# fpga31-serdes-power.net
KiCad netlist of a schematic drawn in Altium Designer
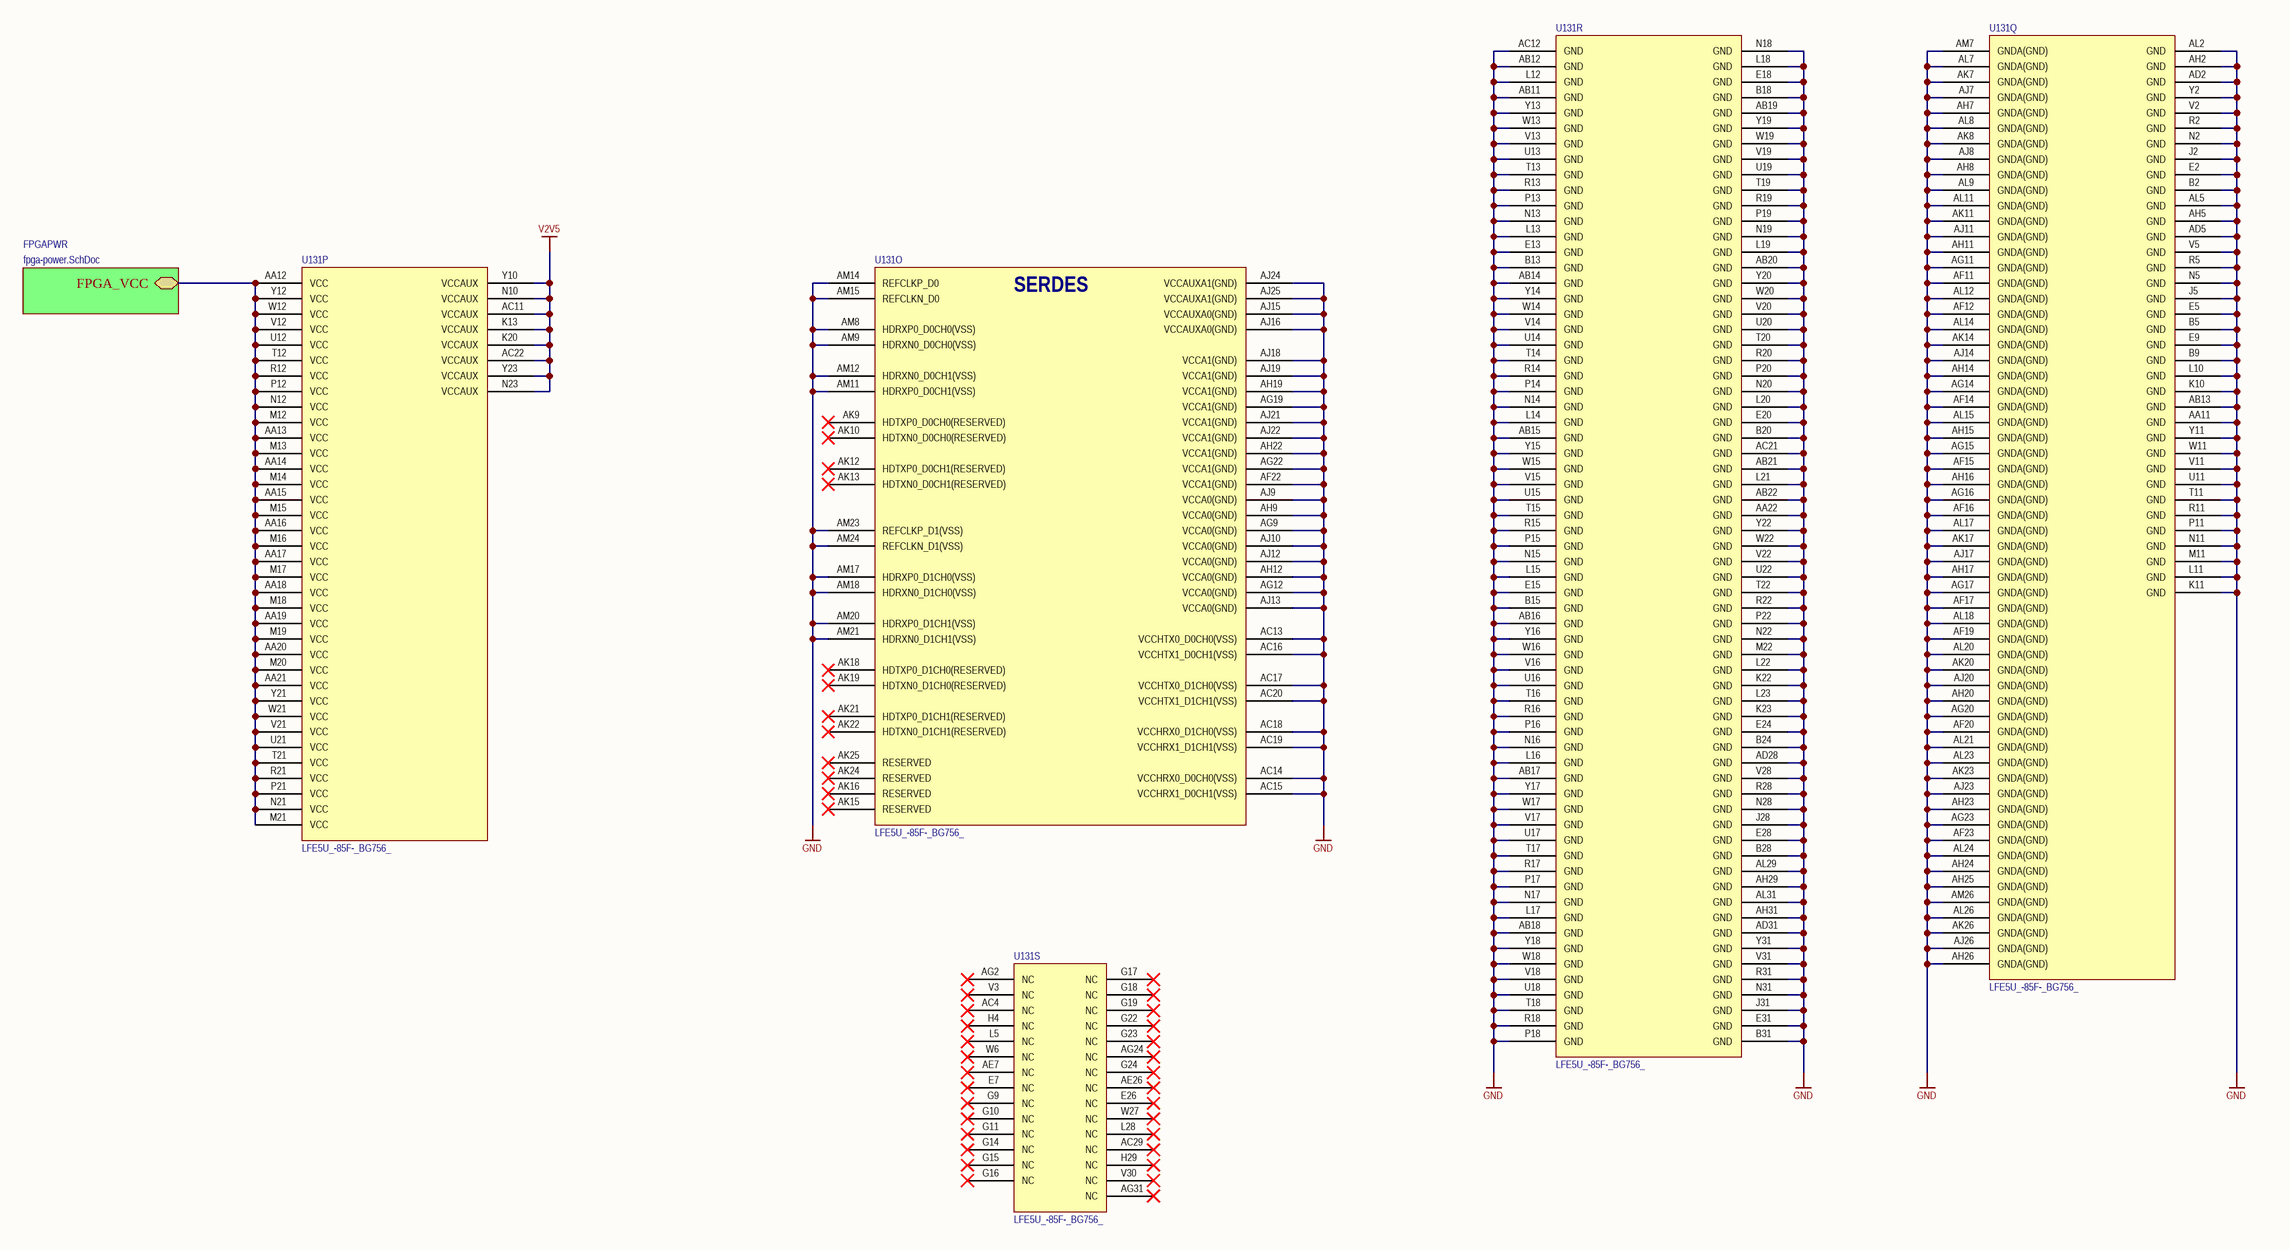
[diagram p0: fpga31-serdes-power.SchDoc]

(export (version "E")
  (design (tool "Eeschema 10.0.6"))
  (components
    (comp (ref "U131")
      (value "LFE5U_-85F-_BG756_")
      (footprint "lattice:caBGA756")
      (description "ECP5 FPGA, 85k LUT, 756-caBGA")
      (fields (field (name "MANUFACTURER") "Lattice Semiconductor"))
      (libsource (lib "lattice") (part "LFE5U_-85F-_BG756_"))
    )
  )
  (nets
    (net (code "1") (name "/FPGA_VCC") (class "Default")
      (node (ref "U131") (pin "AA12") (pinfunction "VCC_AA12") (pintype "power_in"))
      (node (ref "U131") (pin "AA13") (pinfunction "VCC_AA13") (pintype "power_in"))
      (node (ref "U131") (pin "AA14") (pinfunction "VCC_AA14") (pintype "power_in"))
      (node (ref "U131") (pin "AA15") (pinfunction "VCC_AA15") (pintype "power_in"))
      (node (ref "U131") (pin "AA16") (pinfunction "VCC_AA16") (pintype "power_in"))
      (node (ref "U131") (pin "AA17") (pinfunction "VCC_AA17") (pintype "power_in"))
      (node (ref "U131") (pin "AA18") (pinfunction "VCC_AA18") (pintype "power_in"))
      (node (ref "U131") (pin "AA19") (pinfunction "VCC_AA19") (pintype "power_in"))
      (node (ref "U131") (pin "AA20") (pinfunction "VCC_AA20") (pintype "power_in"))
      (node (ref "U131") (pin "AA21") (pinfunction "VCC_AA21") (pintype "power_in"))
      (node (ref "U131") (pin "M12") (pinfunction "VCC_M12") (pintype "power_in"))
      (node (ref "U131") (pin "M13") (pinfunction "VCC_M13") (pintype "power_in"))
      (node (ref "U131") (pin "M14") (pinfunction "VCC_M14") (pintype "power_in"))
      (node (ref "U131") (pin "M15") (pinfunction "VCC_M15") (pintype "power_in"))
      (node (ref "U131") (pin "M16") (pinfunction "VCC_M16") (pintype "power_in"))
      (node (ref "U131") (pin "M17") (pinfunction "VCC_M17") (pintype "power_in"))
      (node (ref "U131") (pin "M18") (pinfunction "VCC_M18") (pintype "power_in"))
      (node (ref "U131") (pin "M19") (pinfunction "VCC_M19") (pintype "power_in"))
      (node (ref "U131") (pin "M20") (pinfunction "VCC_M20") (pintype "power_in"))
      (node (ref "U131") (pin "M21") (pinfunction "VCC_M21") (pintype "power_in"))
      (node (ref "U131") (pin "N12") (pinfunction "VCC_N12") (pintype "power_in"))
      (node (ref "U131") (pin "N21") (pinfunction "VCC_N21") (pintype "power_in"))
      (node (ref "U131") (pin "P12") (pinfunction "VCC_P12") (pintype "power_in"))
      (node (ref "U131") (pin "P21") (pinfunction "VCC_P21") (pintype "power_in"))
      (node (ref "U131") (pin "R12") (pinfunction "VCC_R12") (pintype "power_in"))
      (node (ref "U131") (pin "R21") (pinfunction "VCC_R21") (pintype "power_in"))
      (node (ref "U131") (pin "T12") (pinfunction "VCC_T12") (pintype "power_in"))
      (node (ref "U131") (pin "T21") (pinfunction "VCC_T21") (pintype "power_in"))
      (node (ref "U131") (pin "U12") (pinfunction "VCC_U12") (pintype "power_in"))
      (node (ref "U131") (pin "U21") (pinfunction "VCC_U21") (pintype "power_in"))
      (node (ref "U131") (pin "V12") (pinfunction "VCC_V12") (pintype "power_in"))
      (node (ref "U131") (pin "V21") (pinfunction "VCC_V21") (pintype "power_in"))
      (node (ref "U131") (pin "W12") (pinfunction "VCC_W12") (pintype "power_in"))
      (node (ref "U131") (pin "W21") (pinfunction "VCC_W21") (pintype "power_in"))
      (node (ref "U131") (pin "Y12") (pinfunction "VCC_Y12") (pintype "power_in"))
      (node (ref "U131") (pin "Y21") (pinfunction "VCC_Y21") (pintype "power_in"))
    )
    (net (code "2") (name "GND") (class "Default")
      (node (ref "U131") (pin "AA11") (pinfunction "GND_AA11") (pintype "power_in"))
      (node (ref "U131") (pin "AA22") (pinfunction "GND_AA22") (pintype "power_in"))
      (node (ref "U131") (pin "AB11") (pinfunction "GND_AB11") (pintype "power_in"))
      (node (ref "U131") (pin "AB12") (pinfunction "GND_AB12") (pintype "power_in"))
      (node (ref "U131") (pin "AB13") (pinfunction "GND_AB13") (pintype "power_in"))
      (node (ref "U131") (pin "AB14") (pinfunction "GND_AB14") (pintype "power_in"))
      (node (ref "U131") (pin "AB15") (pinfunction "GND_AB15") (pintype "power_in"))
      (node (ref "U131") (pin "AB16") (pinfunction "GND_AB16") (pintype "power_in"))
      (node (ref "U131") (pin "AB17") (pinfunction "GND_AB17") (pintype "power_in"))
      (node (ref "U131") (pin "AB18") (pinfunction "GND_AB18") (pintype "power_in"))
      (node (ref "U131") (pin "AB19") (pinfunction "GND_AB19") (pintype "power_in"))
      (node (ref "U131") (pin "AB20") (pinfunction "GND_AB20") (pintype "power_in"))
      (node (ref "U131") (pin "AB21") (pinfunction "GND_AB21") (pintype "power_in"))
      (node (ref "U131") (pin "AB22") (pinfunction "GND_AB22") (pintype "power_in"))
      (node (ref "U131") (pin "AC12") (pinfunction "GND_AC12") (pintype "power_in"))
      (node (ref "U131") (pin "AC13") (pinfunction "VCCHTX0_D0CH0(VSS)_AC13") (pintype "power_in"))
      (node (ref "U131") (pin "AC14") (pinfunction "VCCHRX0_D0CH0(VSS)_AC14") (pintype "power_in"))
      (node (ref "U131") (pin "AC15") (pinfunction "VCCHRX1_D0CH1(VSS)_AC15") (pintype "power_in"))
      (node (ref "U131") (pin "AC16") (pinfunction "VCCHTX1_D0CH1(VSS)_AC16") (pintype "power_in"))
      (node (ref "U131") (pin "AC17") (pinfunction "VCCHTX0_D1CH0(VSS)_AC17") (pintype "power_in"))
      (node (ref "U131") (pin "AC18") (pinfunction "VCCHRX0_D1CH0(VSS)_AC18") (pintype "power_in"))
      (node (ref "U131") (pin "AC19") (pinfunction "VCCHRX1_D1CH1(VSS)_AC19") (pintype "power_in"))
      (node (ref "U131") (pin "AC20") (pinfunction "VCCHTX1_D1CH1(VSS)_AC20") (pintype "power_in"))
      (node (ref "U131") (pin "AC21") (pinfunction "GND_AC21") (pintype "power_in"))
      (node (ref "U131") (pin "AD2") (pinfunction "GND_AD2") (pintype "power_in"))
      (node (ref "U131") (pin "AD28") (pinfunction "GND_AD28") (pintype "power_in"))
      (node (ref "U131") (pin "AD31") (pinfunction "GND_AD31") (pintype "power_in"))
      (node (ref "U131") (pin "AD5") (pinfunction "GND_AD5") (pintype "power_in"))
      (node (ref "U131") (pin "AF11") (pinfunction "GNDA(GND)_AF11") (pintype "power_in"))
      (node (ref "U131") (pin "AF12") (pinfunction "GNDA(GND)_AF12") (pintype "power_in"))
      (node (ref "U131") (pin "AF14") (pinfunction "GNDA(GND)_AF14") (pintype "power_in"))
      (node (ref "U131") (pin "AF15") (pinfunction "GNDA(GND)_AF15") (pintype "power_in"))
      (node (ref "U131") (pin "AF16") (pinfunction "GNDA(GND)_AF16") (pintype "power_in"))
      (node (ref "U131") (pin "AF17") (pinfunction "GNDA(GND)_AF17") (pintype "power_in"))
      (node (ref "U131") (pin "AF19") (pinfunction "GNDA(GND)_AF19") (pintype "power_in"))
      (node (ref "U131") (pin "AF20") (pinfunction "GNDA(GND)_AF20") (pintype "power_in"))
      (node (ref "U131") (pin "AF22") (pinfunction "VCCA1(GND)_AF22") (pintype "power_in"))
      (node (ref "U131") (pin "AF23") (pinfunction "GNDA(GND)_AF23") (pintype "power_in"))
      (node (ref "U131") (pin "AG11") (pinfunction "GNDA(GND)_AG11") (pintype "power_in"))
      (node (ref "U131") (pin "AG12") (pinfunction "VCCA0(GND)_AG12") (pintype "power_in"))
      (node (ref "U131") (pin "AG14") (pinfunction "GNDA(GND)_AG14") (pintype "power_in"))
      (node (ref "U131") (pin "AG15") (pinfunction "GNDA(GND)_AG15") (pintype "power_in"))
      (node (ref "U131") (pin "AG16") (pinfunction "GNDA(GND)_AG16") (pintype "power_in"))
      (node (ref "U131") (pin "AG17") (pinfunction "GNDA(GND)_AG17") (pintype "power_in"))
      (node (ref "U131") (pin "AG19") (pinfunction "VCCA1(GND)_AG19") (pintype "power_in"))
      (node (ref "U131") (pin "AG20") (pinfunction "GNDA(GND)_AG20") (pintype "power_in"))
      (node (ref "U131") (pin "AG22") (pinfunction "VCCA1(GND)_AG22") (pintype "power_in"))
      (node (ref "U131") (pin "AG23") (pinfunction "GNDA(GND)_AG23") (pintype "power_in"))
      (node (ref "U131") (pin "AG9") (pinfunction "VCCA0(GND)_AG9") (pintype "power_in"))
      (node (ref "U131") (pin "AH11") (pinfunction "GNDA(GND)_AH11") (pintype "power_in"))
      (node (ref "U131") (pin "AH12") (pinfunction "VCCA0(GND)_AH12") (pintype "power_in"))
      (node (ref "U131") (pin "AH14") (pinfunction "GNDA(GND)_AH14") (pintype "power_in"))
      (node (ref "U131") (pin "AH15") (pinfunction "GNDA(GND)_AH15") (pintype "power_in"))
      (node (ref "U131") (pin "AH16") (pinfunction "GNDA(GND)_AH16") (pintype "power_in"))
      (node (ref "U131") (pin "AH17") (pinfunction "GNDA(GND)_AH17") (pintype "power_in"))
      (node (ref "U131") (pin "AH19") (pinfunction "VCCA1(GND)_AH19") (pintype "power_in"))
      (node (ref "U131") (pin "AH2") (pinfunction "GND_AH2") (pintype "power_in"))
      (node (ref "U131") (pin "AH20") (pinfunction "GNDA(GND)_AH20") (pintype "power_in"))
      (node (ref "U131") (pin "AH22") (pinfunction "VCCA1(GND)_AH22") (pintype "power_in"))
      (node (ref "U131") (pin "AH23") (pinfunction "GNDA(GND)_AH23") (pintype "power_in"))
      (node (ref "U131") (pin "AH24") (pinfunction "GNDA(GND)_AH24") (pintype "power_in"))
      (node (ref "U131") (pin "AH25") (pinfunction "GNDA(GND)_AH25") (pintype "power_in"))
      (node (ref "U131") (pin "AH26") (pinfunction "GNDA(GND)_AH26") (pintype "power_in"))
      (node (ref "U131") (pin "AH29") (pinfunction "GND_AH29") (pintype "power_in"))
      (node (ref "U131") (pin "AH31") (pinfunction "GND_AH31") (pintype "power_in"))
      (node (ref "U131") (pin "AH5") (pinfunction "GND_AH5") (pintype "power_in"))
      (node (ref "U131") (pin "AH7") (pinfunction "GNDA(GND)_AH7") (pintype "power_in"))
      (node (ref "U131") (pin "AH8") (pinfunction "GNDA(GND)_AH8") (pintype "power_in"))
      (node (ref "U131") (pin "AH9") (pinfunction "VCCA0(GND)_AH9") (pintype "power_in"))
      (node (ref "U131") (pin "AJ10") (pinfunction "VCCA0(GND)_AJ10") (pintype "power_in"))
      (node (ref "U131") (pin "AJ11") (pinfunction "GNDA(GND)_AJ11") (pintype "power_in"))
      (node (ref "U131") (pin "AJ12") (pinfunction "VCCA0(GND)_AJ12") (pintype "power_in"))
      (node (ref "U131") (pin "AJ13") (pinfunction "VCCA0(GND)_AJ13") (pintype "power_in"))
      (node (ref "U131") (pin "AJ14") (pinfunction "GNDA(GND)_AJ14") (pintype "power_in"))
      (node (ref "U131") (pin "AJ15") (pinfunction "VCCAUXA0(GND)_AJ15") (pintype "power_in"))
      (node (ref "U131") (pin "AJ16") (pinfunction "VCCAUXA0(GND)_AJ16") (pintype "power_in"))
      (node (ref "U131") (pin "AJ17") (pinfunction "GNDA(GND)_AJ17") (pintype "power_in"))
      (node (ref "U131") (pin "AJ18") (pinfunction "VCCA1(GND)_AJ18") (pintype "power_in"))
      (node (ref "U131") (pin "AJ19") (pinfunction "VCCA1(GND)_AJ19") (pintype "power_in"))
      (node (ref "U131") (pin "AJ20") (pinfunction "GNDA(GND)_AJ20") (pintype "power_in"))
      (node (ref "U131") (pin "AJ21") (pinfunction "VCCA1(GND)_AJ21") (pintype "power_in"))
      (node (ref "U131") (pin "AJ22") (pinfunction "VCCA1(GND)_AJ22") (pintype "power_in"))
      (node (ref "U131") (pin "AJ23") (pinfunction "GNDA(GND)_AJ23") (pintype "power_in"))
      (node (ref "U131") (pin "AJ24") (pinfunction "VCCAUXA1(GND)_AJ24") (pintype "power_in"))
      (node (ref "U131") (pin "AJ25") (pinfunction "VCCAUXA1(GND)_AJ25") (pintype "power_in"))
      (node (ref "U131") (pin "AJ26") (pinfunction "GNDA(GND)_AJ26") (pintype "power_in"))
      (node (ref "U131") (pin "AJ7") (pinfunction "GNDA(GND)_AJ7") (pintype "power_in"))
      (node (ref "U131") (pin "AJ8") (pinfunction "GNDA(GND)_AJ8") (pintype "power_in"))
      (node (ref "U131") (pin "AJ9") (pinfunction "VCCA0(GND)_AJ9") (pintype "power_in"))
      (node (ref "U131") (pin "AK11") (pinfunction "GNDA(GND)_AK11") (pintype "power_in"))
      (node (ref "U131") (pin "AK14") (pinfunction "GNDA(GND)_AK14") (pintype "power_in"))
      (node (ref "U131") (pin "AK17") (pinfunction "GNDA(GND)_AK17") (pintype "power_in"))
      (node (ref "U131") (pin "AK20") (pinfunction "GNDA(GND)_AK20") (pintype "power_in"))
      (node (ref "U131") (pin "AK23") (pinfunction "GNDA(GND)_AK23") (pintype "power_in"))
      (node (ref "U131") (pin "AK26") (pinfunction "GNDA(GND)_AK26") (pintype "power_in"))
      (node (ref "U131") (pin "AK7") (pinfunction "GNDA(GND)_AK7") (pintype "power_in"))
      (node (ref "U131") (pin "AK8") (pinfunction "GNDA(GND)_AK8") (pintype "power_in"))
      (node (ref "U131") (pin "AL11") (pinfunction "GNDA(GND)_AL11") (pintype "power_in"))
      (node (ref "U131") (pin "AL12") (pinfunction "GNDA(GND)_AL12") (pintype "power_in"))
      (node (ref "U131") (pin "AL14") (pinfunction "GNDA(GND)_AL14") (pintype "power_in"))
      (node (ref "U131") (pin "AL15") (pinfunction "GNDA(GND)_AL15") (pintype "power_in"))
      (node (ref "U131") (pin "AL17") (pinfunction "GNDA(GND)_AL17") (pintype "power_in"))
      (node (ref "U131") (pin "AL18") (pinfunction "GNDA(GND)_AL18") (pintype "power_in"))
      (node (ref "U131") (pin "AL2") (pinfunction "GND_AL2") (pintype "power_in"))
      (node (ref "U131") (pin "AL20") (pinfunction "GNDA(GND)_AL20") (pintype "power_in"))
      (node (ref "U131") (pin "AL21") (pinfunction "GNDA(GND)_AL21") (pintype "power_in"))
      (node (ref "U131") (pin "AL23") (pinfunction "GNDA(GND)_AL23") (pintype "power_in"))
      (node (ref "U131") (pin "AL24") (pinfunction "GNDA(GND)_AL24") (pintype "power_in"))
      (node (ref "U131") (pin "AL26") (pinfunction "GNDA(GND)_AL26") (pintype "power_in"))
      (node (ref "U131") (pin "AL29") (pinfunction "GND_AL29") (pintype "power_in"))
      (node (ref "U131") (pin "AL31") (pinfunction "GND_AL31") (pintype "power_in"))
      (node (ref "U131") (pin "AL5") (pinfunction "GND_AL5") (pintype "power_in"))
      (node (ref "U131") (pin "AL7") (pinfunction "GNDA(GND)_AL7") (pintype "power_in"))
      (node (ref "U131") (pin "AL8") (pinfunction "GNDA(GND)_AL8") (pintype "power_in"))
      (node (ref "U131") (pin "AL9") (pinfunction "GNDA(GND)_AL9") (pintype "power_in"))
      (node (ref "U131") (pin "AM11") (pinfunction "HDRXP0_D0CH1(VSS)_AM11") (pintype "passive"))
      (node (ref "U131") (pin "AM12") (pinfunction "HDRXN0_D0CH1(VSS)_AM12") (pintype "passive"))
      (node (ref "U131") (pin "AM14") (pinfunction "REFCLKP_D0_AM14") (pintype "passive"))
      (node (ref "U131") (pin "AM15") (pinfunction "REFCLKN_D0_AM15") (pintype "passive"))
      (node (ref "U131") (pin "AM17") (pinfunction "HDRXP0_D1CH0(VSS)_AM17") (pintype "passive"))
      (node (ref "U131") (pin "AM18") (pinfunction "HDRXN0_D1CH0(VSS)_AM18") (pintype "passive"))
      (node (ref "U131") (pin "AM20") (pinfunction "HDRXP0_D1CH1(VSS)_AM20") (pintype "passive"))
      (node (ref "U131") (pin "AM21") (pinfunction "HDRXN0_D1CH1(VSS)_AM21") (pintype "passive"))
      (node (ref "U131") (pin "AM23") (pinfunction "REFCLKP_D1(VSS)_AM23") (pintype "passive"))
      (node (ref "U131") (pin "AM24") (pinfunction "REFCLKN_D1(VSS)_AM24") (pintype "passive"))
      (node (ref "U131") (pin "AM26") (pinfunction "GNDA(GND)_AM26") (pintype "power_in"))
      (node (ref "U131") (pin "AM7") (pinfunction "GNDA(GND)_AM7") (pintype "power_in"))
      (node (ref "U131") (pin "AM8") (pinfunction "HDRXP0_D0CH0(VSS)_AM8") (pintype "passive"))
      (node (ref "U131") (pin "AM9") (pinfunction "HDRXN0_D0CH0(VSS)_AM9") (pintype "passive"))
      (node (ref "U131") (pin "B13") (pinfunction "GND_B13") (pintype "power_in"))
      (node (ref "U131") (pin "B15") (pinfunction "GND_B15") (pintype "power_in"))
      (node (ref "U131") (pin "B18") (pinfunction "GND_B18") (pintype "power_in"))
      (node (ref "U131") (pin "B2") (pinfunction "GND_B2") (pintype "power_in"))
      (node (ref "U131") (pin "B20") (pinfunction "GND_B20") (pintype "power_in"))
      (node (ref "U131") (pin "B24") (pinfunction "GND_B24") (pintype "power_in"))
      (node (ref "U131") (pin "B28") (pinfunction "GND_B28") (pintype "power_in"))
      (node (ref "U131") (pin "B31") (pinfunction "GND_B31") (pintype "power_in"))
      (node (ref "U131") (pin "B5") (pinfunction "GND_B5") (pintype "power_in"))
      (node (ref "U131") (pin "B9") (pinfunction "GND_B9") (pintype "power_in"))
      (node (ref "U131") (pin "E13") (pinfunction "GND_E13") (pintype "power_in"))
      (node (ref "U131") (pin "E15") (pinfunction "GND_E15") (pintype "power_in"))
      (node (ref "U131") (pin "E18") (pinfunction "GND_E18") (pintype "power_in"))
      (node (ref "U131") (pin "E2") (pinfunction "GND_E2") (pintype "power_in"))
      (node (ref "U131") (pin "E20") (pinfunction "GND_E20") (pintype "power_in"))
      (node (ref "U131") (pin "E24") (pinfunction "GND_E24") (pintype "power_in"))
      (node (ref "U131") (pin "E28") (pinfunction "GND_E28") (pintype "power_in"))
      (node (ref "U131") (pin "E31") (pinfunction "GND_E31") (pintype "power_in"))
      (node (ref "U131") (pin "E5") (pinfunction "GND_E5") (pintype "power_in"))
      (node (ref "U131") (pin "E9") (pinfunction "GND_E9") (pintype "power_in"))
      (node (ref "U131") (pin "J2") (pinfunction "GND_J2") (pintype "power_in"))
      (node (ref "U131") (pin "J28") (pinfunction "GND_J28") (pintype "power_in"))
      (node (ref "U131") (pin "J31") (pinfunction "GND_J31") (pintype "power_in"))
      (node (ref "U131") (pin "J5") (pinfunction "GND_J5") (pintype "power_in"))
      (node (ref "U131") (pin "K10") (pinfunction "GND_K10") (pintype "power_in"))
      (node (ref "U131") (pin "K11") (pinfunction "GND_K11") (pintype "power_in"))
      (node (ref "U131") (pin "K22") (pinfunction "GND_K22") (pintype "power_in"))
      (node (ref "U131") (pin "K23") (pinfunction "GND_K23") (pintype "power_in"))
      (node (ref "U131") (pin "L10") (pinfunction "GND_L10") (pintype "power_in"))
      (node (ref "U131") (pin "L11") (pinfunction "GND_L11") (pintype "power_in"))
      (node (ref "U131") (pin "L12") (pinfunction "GND_L12") (pintype "power_in"))
      (node (ref "U131") (pin "L13") (pinfunction "GND_L13") (pintype "power_in"))
      (node (ref "U131") (pin "L14") (pinfunction "GND_L14") (pintype "power_in"))
      (node (ref "U131") (pin "L15") (pinfunction "GND_L15") (pintype "power_in"))
      (node (ref "U131") (pin "L16") (pinfunction "GND_L16") (pintype "power_in"))
      (node (ref "U131") (pin "L17") (pinfunction "GND_L17") (pintype "power_in"))
      (node (ref "U131") (pin "L18") (pinfunction "GND_L18") (pintype "power_in"))
      (node (ref "U131") (pin "L19") (pinfunction "GND_L19") (pintype "power_in"))
      (node (ref "U131") (pin "L20") (pinfunction "GND_L20") (pintype "power_in"))
      (node (ref "U131") (pin "L21") (pinfunction "GND_L21") (pintype "power_in"))
      (node (ref "U131") (pin "L22") (pinfunction "GND_L22") (pintype "power_in"))
      (node (ref "U131") (pin "L23") (pinfunction "GND_L23") (pintype "power_in"))
      (node (ref "U131") (pin "M11") (pinfunction "GND_M11") (pintype "power_in"))
      (node (ref "U131") (pin "M22") (pinfunction "GND_M22") (pintype "power_in"))
      (node (ref "U131") (pin "N11") (pinfunction "GND_N11") (pintype "power_in"))
      (node (ref "U131") (pin "N13") (pinfunction "GND_N13") (pintype "power_in"))
      (node (ref "U131") (pin "N14") (pinfunction "GND_N14") (pintype "power_in"))
      (node (ref "U131") (pin "N15") (pinfunction "GND_N15") (pintype "power_in"))
      (node (ref "U131") (pin "N16") (pinfunction "GND_N16") (pintype "power_in"))
      (node (ref "U131") (pin "N17") (pinfunction "GND_N17") (pintype "power_in"))
      (node (ref "U131") (pin "N18") (pinfunction "GND_N18") (pintype "power_in"))
      (node (ref "U131") (pin "N19") (pinfunction "GND_N19") (pintype "power_in"))
      (node (ref "U131") (pin "N2") (pinfunction "GND_N2") (pintype "power_in"))
      (node (ref "U131") (pin "N20") (pinfunction "GND_N20") (pintype "power_in"))
      (node (ref "U131") (pin "N22") (pinfunction "GND_N22") (pintype "power_in"))
      (node (ref "U131") (pin "N28") (pinfunction "GND_N28") (pintype "power_in"))
      (node (ref "U131") (pin "N31") (pinfunction "GND_N31") (pintype "power_in"))
      (node (ref "U131") (pin "N5") (pinfunction "GND_N5") (pintype "power_in"))
      (node (ref "U131") (pin "P11") (pinfunction "GND_P11") (pintype "power_in"))
      (node (ref "U131") (pin "P13") (pinfunction "GND_P13") (pintype "power_in"))
      (node (ref "U131") (pin "P14") (pinfunction "GND_P14") (pintype "power_in"))
      (node (ref "U131") (pin "P15") (pinfunction "GND_P15") (pintype "power_in"))
      (node (ref "U131") (pin "P16") (pinfunction "GND_P16") (pintype "power_in"))
      (node (ref "U131") (pin "P17") (pinfunction "GND_P17") (pintype "power_in"))
      (node (ref "U131") (pin "P18") (pinfunction "GND_P18") (pintype "power_in"))
      (node (ref "U131") (pin "P19") (pinfunction "GND_P19") (pintype "power_in"))
      (node (ref "U131") (pin "P20") (pinfunction "GND_P20") (pintype "power_in"))
      (node (ref "U131") (pin "P22") (pinfunction "GND_P22") (pintype "power_in"))
      (node (ref "U131") (pin "R11") (pinfunction "GND_R11") (pintype "power_in"))
      (node (ref "U131") (pin "R13") (pinfunction "GND_R13") (pintype "power_in"))
      (node (ref "U131") (pin "R14") (pinfunction "GND_R14") (pintype "power_in"))
      (node (ref "U131") (pin "R15") (pinfunction "GND_R15") (pintype "power_in"))
      (node (ref "U131") (pin "R16") (pinfunction "GND_R16") (pintype "power_in"))
      (node (ref "U131") (pin "R17") (pinfunction "GND_R17") (pintype "power_in"))
      (node (ref "U131") (pin "R18") (pinfunction "GND_R18") (pintype "power_in"))
      (node (ref "U131") (pin "R19") (pinfunction "GND_R19") (pintype "power_in"))
      (node (ref "U131") (pin "R2") (pinfunction "GND_R2") (pintype "power_in"))
      (node (ref "U131") (pin "R20") (pinfunction "GND_R20") (pintype "power_in"))
      (node (ref "U131") (pin "R22") (pinfunction "GND_R22") (pintype "power_in"))
      (node (ref "U131") (pin "R28") (pinfunction "GND_R28") (pintype "power_in"))
      (node (ref "U131") (pin "R31") (pinfunction "GND_R31") (pintype "power_in"))
      (node (ref "U131") (pin "R5") (pinfunction "GND_R5") (pintype "power_in"))
      (node (ref "U131") (pin "T11") (pinfunction "GND_T11") (pintype "power_in"))
      (node (ref "U131") (pin "T13") (pinfunction "GND_T13") (pintype "power_in"))
      (node (ref "U131") (pin "T14") (pinfunction "GND_T14") (pintype "power_in"))
      (node (ref "U131") (pin "T15") (pinfunction "GND_T15") (pintype "power_in"))
      (node (ref "U131") (pin "T16") (pinfunction "GND_T16") (pintype "power_in"))
      (node (ref "U131") (pin "T17") (pinfunction "GND_T17") (pintype "power_in"))
      (node (ref "U131") (pin "T18") (pinfunction "GND_T18") (pintype "power_in"))
      (node (ref "U131") (pin "T19") (pinfunction "GND_T19") (pintype "power_in"))
      (node (ref "U131") (pin "T20") (pinfunction "GND_T20") (pintype "power_in"))
      (node (ref "U131") (pin "T22") (pinfunction "GND_T22") (pintype "power_in"))
      (node (ref "U131") (pin "U11") (pinfunction "GND_U11") (pintype "power_in"))
      (node (ref "U131") (pin "U13") (pinfunction "GND_U13") (pintype "power_in"))
      (node (ref "U131") (pin "U14") (pinfunction "GND_U14") (pintype "power_in"))
      (node (ref "U131") (pin "U15") (pinfunction "GND_U15") (pintype "power_in"))
      (node (ref "U131") (pin "U16") (pinfunction "GND_U16") (pintype "power_in"))
      (node (ref "U131") (pin "U17") (pinfunction "GND_U17") (pintype "power_in"))
      (node (ref "U131") (pin "U18") (pinfunction "GND_U18") (pintype "power_in"))
      (node (ref "U131") (pin "U19") (pinfunction "GND_U19") (pintype "power_in"))
      (node (ref "U131") (pin "U20") (pinfunction "GND_U20") (pintype "power_in"))
      (node (ref "U131") (pin "U22") (pinfunction "GND_U22") (pintype "power_in"))
      (node (ref "U131") (pin "V11") (pinfunction "GND_V11") (pintype "power_in"))
      (node (ref "U131") (pin "V13") (pinfunction "GND_V13") (pintype "power_in"))
      (node (ref "U131") (pin "V14") (pinfunction "GND_V14") (pintype "power_in"))
      (node (ref "U131") (pin "V15") (pinfunction "GND_V15") (pintype "power_in"))
      (node (ref "U131") (pin "V16") (pinfunction "GND_V16") (pintype "power_in"))
      (node (ref "U131") (pin "V17") (pinfunction "GND_V17") (pintype "power_in"))
      (node (ref "U131") (pin "V18") (pinfunction "GND_V18") (pintype "power_in"))
      (node (ref "U131") (pin "V19") (pinfunction "GND_V19") (pintype "power_in"))
      (node (ref "U131") (pin "V2") (pinfunction "GND_V2") (pintype "power_in"))
      (node (ref "U131") (pin "V20") (pinfunction "GND_V20") (pintype "power_in"))
      (node (ref "U131") (pin "V22") (pinfunction "GND_V22") (pintype "power_in"))
      (node (ref "U131") (pin "V28") (pinfunction "GND_V28") (pintype "power_in"))
      (node (ref "U131") (pin "V31") (pinfunction "GND_V31") (pintype "power_in"))
      (node (ref "U131") (pin "V5") (pinfunction "GND_V5") (pintype "power_in"))
      (node (ref "U131") (pin "W11") (pinfunction "GND_W11") (pintype "power_in"))
      (node (ref "U131") (pin "W13") (pinfunction "GND_W13") (pintype "power_in"))
      (node (ref "U131") (pin "W14") (pinfunction "GND_W14") (pintype "power_in"))
      (node (ref "U131") (pin "W15") (pinfunction "GND_W15") (pintype "power_in"))
      (node (ref "U131") (pin "W16") (pinfunction "GND_W16") (pintype "power_in"))
      (node (ref "U131") (pin "W17") (pinfunction "GND_W17") (pintype "power_in"))
      (node (ref "U131") (pin "W18") (pinfunction "GND_W18") (pintype "power_in"))
      (node (ref "U131") (pin "W19") (pinfunction "GND_W19") (pintype "power_in"))
      (node (ref "U131") (pin "W20") (pinfunction "GND_W20") (pintype "power_in"))
      (node (ref "U131") (pin "W22") (pinfunction "GND_W22") (pintype "power_in"))
      (node (ref "U131") (pin "Y11") (pinfunction "GND_Y11") (pintype "power_in"))
      (node (ref "U131") (pin "Y13") (pinfunction "GND_Y13") (pintype "power_in"))
      (node (ref "U131") (pin "Y14") (pinfunction "GND_Y14") (pintype "power_in"))
      (node (ref "U131") (pin "Y15") (pinfunction "GND_Y15") (pintype "power_in"))
      (node (ref "U131") (pin "Y16") (pinfunction "GND_Y16") (pintype "power_in"))
      (node (ref "U131") (pin "Y17") (pinfunction "GND_Y17") (pintype "power_in"))
      (node (ref "U131") (pin "Y18") (pinfunction "GND_Y18") (pintype "power_in"))
      (node (ref "U131") (pin "Y19") (pinfunction "GND_Y19") (pintype "power_in"))
      (node (ref "U131") (pin "Y2") (pinfunction "GND_Y2") (pintype "power_in"))
      (node (ref "U131") (pin "Y20") (pinfunction "GND_Y20") (pintype "power_in"))
      (node (ref "U131") (pin "Y22") (pinfunction "GND_Y22") (pintype "power_in"))
      (node (ref "U131") (pin "Y31") (pinfunction "GND_Y31") (pintype "power_in"))
    )
    (net (code "3") (name "V2V5") (class "Default")
      (node (ref "U131") (pin "AC11") (pinfunction "VCCAUX_AC11") (pintype "power_in"))
      (node (ref "U131") (pin "AC22") (pinfunction "VCCAUX_AC22") (pintype "power_in"))
      (node (ref "U131") (pin "K13") (pinfunction "VCCAUX_K13") (pintype "power_in"))
      (node (ref "U131") (pin "K20") (pinfunction "VCCAUX_K20") (pintype "power_in"))
      (node (ref "U131") (pin "N10") (pinfunction "VCCAUX_N10") (pintype "power_in"))
      (node (ref "U131") (pin "N23") (pinfunction "VCCAUX_N23") (pintype "power_in"))
      (node (ref "U131") (pin "Y10") (pinfunction "VCCAUX_Y10") (pintype "power_in"))
      (node (ref "U131") (pin "Y23") (pinfunction "VCCAUX_Y23") (pintype "power_in"))
    )
    (net (code "4") (name "unconnected-(U131O-HDTXN0_D0CH0(RESERVED)-PadAK10)") (class "Default")
      (node (ref "U131") (pin "AK10") (pinfunction "HDTXN0_D0CH0(RESERVED)_AK10") (pintype "passive+no_connect"))
    )
    (net (code "5") (name "unconnected-(U131O-HDTXN0_D0CH1(RESERVED)-PadAK13)") (class "Default")
      (node (ref "U131") (pin "AK13") (pinfunction "HDTXN0_D0CH1(RESERVED)_AK13") (pintype "passive+no_connect"))
    )
    (net (code "6") (name "unconnected-(U131O-HDTXN0_D1CH0(RESERVED)-PadAK19)") (class "Default")
      (node (ref "U131") (pin "AK19") (pinfunction "HDTXN0_D1CH0(RESERVED)_AK19") (pintype "passive+no_connect"))
    )
    (net (code "7") (name "unconnected-(U131O-HDTXN0_D1CH1(RESERVED)-PadAK22)") (class "Default")
      (node (ref "U131") (pin "AK22") (pinfunction "HDTXN0_D1CH1(RESERVED)_AK22") (pintype "passive+no_connect"))
    )
    (net (code "8") (name "unconnected-(U131O-HDTXP0_D0CH0(RESERVED)-PadAK9)") (class "Default")
      (node (ref "U131") (pin "AK9") (pinfunction "HDTXP0_D0CH0(RESERVED)_AK9") (pintype "passive+no_connect"))
    )
    (net (code "9") (name "unconnected-(U131O-HDTXP0_D0CH1(RESERVED)-PadAK12)") (class "Default")
      (node (ref "U131") (pin "AK12") (pinfunction "HDTXP0_D0CH1(RESERVED)_AK12") (pintype "passive+no_connect"))
    )
    (net (code "10") (name "unconnected-(U131O-HDTXP0_D1CH0(RESERVED)-PadAK18)") (class "Default")
      (node (ref "U131") (pin "AK18") (pinfunction "HDTXP0_D1CH0(RESERVED)_AK18") (pintype "passive+no_connect"))
    )
    (net (code "11") (name "unconnected-(U131O-HDTXP0_D1CH1(RESERVED)-PadAK21)") (class "Default")
      (node (ref "U131") (pin "AK21") (pinfunction "HDTXP0_D1CH1(RESERVED)_AK21") (pintype "passive+no_connect"))
    )
    (net (code "12") (name "unconnected-(U131O-RESERVED-PadAK15)") (class "Default")
      (node (ref "U131") (pin "AK15") (pinfunction "RESERVED_AK15") (pintype "passive+no_connect"))
    )
    (net (code "13") (name "unconnected-(U131O-RESERVED-PadAK16)") (class "Default")
      (node (ref "U131") (pin "AK16") (pinfunction "RESERVED_AK16") (pintype "passive+no_connect"))
    )
    (net (code "14") (name "unconnected-(U131O-RESERVED-PadAK24)") (class "Default")
      (node (ref "U131") (pin "AK24") (pinfunction "RESERVED_AK24") (pintype "passive+no_connect"))
    )
    (net (code "15") (name "unconnected-(U131O-RESERVED-PadAK25)") (class "Default")
      (node (ref "U131") (pin "AK25") (pinfunction "RESERVED_AK25") (pintype "passive+no_connect"))
    )
    (net (code "16") (name "unconnected-(U131S-NC-PadAC4)") (class "Default")
      (node (ref "U131") (pin "AC4") (pinfunction "NC_AC4") (pintype "passive+no_connect"))
    )
    (net (code "17") (name "unconnected-(U131S-NC-PadAC29)") (class "Default")
      (node (ref "U131") (pin "AC29") (pinfunction "NC_AC29") (pintype "passive+no_connect"))
    )
    (net (code "18") (name "unconnected-(U131S-NC-PadAE7)") (class "Default")
      (node (ref "U131") (pin "AE7") (pinfunction "NC_AE7") (pintype "passive+no_connect"))
    )
    (net (code "19") (name "unconnected-(U131S-NC-PadAE26)") (class "Default")
      (node (ref "U131") (pin "AE26") (pinfunction "NC_AE26") (pintype "passive+no_connect"))
    )
    (net (code "20") (name "unconnected-(U131S-NC-PadAG2)") (class "Default")
      (node (ref "U131") (pin "AG2") (pinfunction "NC_AG2") (pintype "passive+no_connect"))
    )
    (net (code "21") (name "unconnected-(U131S-NC-PadAG24)") (class "Default")
      (node (ref "U131") (pin "AG24") (pinfunction "NC_AG24") (pintype "passive+no_connect"))
    )
    (net (code "22") (name "unconnected-(U131S-NC-PadAG31)") (class "Default")
      (node (ref "U131") (pin "AG31") (pinfunction "NC_AG31") (pintype "passive+no_connect"))
    )
    (net (code "23") (name "unconnected-(U131S-NC-PadE7)") (class "Default")
      (node (ref "U131") (pin "E7") (pinfunction "NC_E7") (pintype "passive+no_connect"))
    )
    (net (code "24") (name "unconnected-(U131S-NC-PadE26)") (class "Default")
      (node (ref "U131") (pin "E26") (pinfunction "NC_E26") (pintype "passive+no_connect"))
    )
    (net (code "25") (name "unconnected-(U131S-NC-PadG9)") (class "Default")
      (node (ref "U131") (pin "G9") (pinfunction "NC_G9") (pintype "passive+no_connect"))
    )
    (net (code "26") (name "unconnected-(U131S-NC-PadG10)") (class "Default")
      (node (ref "U131") (pin "G10") (pinfunction "NC_G10") (pintype "passive+no_connect"))
    )
    (net (code "27") (name "unconnected-(U131S-NC-PadG11)") (class "Default")
      (node (ref "U131") (pin "G11") (pinfunction "NC_G11") (pintype "passive+no_connect"))
    )
    (net (code "28") (name "unconnected-(U131S-NC-PadG14)") (class "Default")
      (node (ref "U131") (pin "G14") (pinfunction "NC_G14") (pintype "passive+no_connect"))
    )
    (net (code "29") (name "unconnected-(U131S-NC-PadG15)") (class "Default")
      (node (ref "U131") (pin "G15") (pinfunction "NC_G15") (pintype "passive+no_connect"))
    )
    (net (code "30") (name "unconnected-(U131S-NC-PadG16)") (class "Default")
      (node (ref "U131") (pin "G16") (pinfunction "NC_G16") (pintype "passive+no_connect"))
    )
    (net (code "31") (name "unconnected-(U131S-NC-PadG17)") (class "Default")
      (node (ref "U131") (pin "G17") (pinfunction "NC_G17") (pintype "passive+no_connect"))
    )
    (net (code "32") (name "unconnected-(U131S-NC-PadG18)") (class "Default")
      (node (ref "U131") (pin "G18") (pinfunction "NC_G18") (pintype "passive+no_connect"))
    )
    (net (code "33") (name "unconnected-(U131S-NC-PadG19)") (class "Default")
      (node (ref "U131") (pin "G19") (pinfunction "NC_G19") (pintype "passive+no_connect"))
    )
    (net (code "34") (name "unconnected-(U131S-NC-PadG22)") (class "Default")
      (node (ref "U131") (pin "G22") (pinfunction "NC_G22") (pintype "passive+no_connect"))
    )
    (net (code "35") (name "unconnected-(U131S-NC-PadG23)") (class "Default")
      (node (ref "U131") (pin "G23") (pinfunction "NC_G23") (pintype "passive+no_connect"))
    )
    (net (code "36") (name "unconnected-(U131S-NC-PadG24)") (class "Default")
      (node (ref "U131") (pin "G24") (pinfunction "NC_G24") (pintype "passive+no_connect"))
    )
    (net (code "37") (name "unconnected-(U131S-NC-PadH4)") (class "Default")
      (node (ref "U131") (pin "H4") (pinfunction "NC_H4") (pintype "passive+no_connect"))
    )
    (net (code "38") (name "unconnected-(U131S-NC-PadH29)") (class "Default")
      (node (ref "U131") (pin "H29") (pinfunction "NC_H29") (pintype "passive+no_connect"))
    )
    (net (code "39") (name "unconnected-(U131S-NC-PadL5)") (class "Default")
      (node (ref "U131") (pin "L5") (pinfunction "NC_L5") (pintype "passive+no_connect"))
    )
    (net (code "40") (name "unconnected-(U131S-NC-PadL28)") (class "Default")
      (node (ref "U131") (pin "L28") (pinfunction "NC_L28") (pintype "passive+no_connect"))
    )
    (net (code "41") (name "unconnected-(U131S-NC-PadV3)") (class "Default")
      (node (ref "U131") (pin "V3") (pinfunction "NC_V3") (pintype "passive+no_connect"))
    )
    (net (code "42") (name "unconnected-(U131S-NC-PadV30)") (class "Default")
      (node (ref "U131") (pin "V30") (pinfunction "NC_V30") (pintype "passive+no_connect"))
    )
    (net (code "43") (name "unconnected-(U131S-NC-PadW6)") (class "Default")
      (node (ref "U131") (pin "W6") (pinfunction "NC_W6") (pintype "passive+no_connect"))
    )
    (net (code "44") (name "unconnected-(U131S-NC-PadW27)") (class "Default")
      (node (ref "U131") (pin "W27") (pinfunction "NC_W27") (pintype "passive+no_connect"))
    )
  )
)
